# Ekoplazm.net
KiCad netlist of a schematic drawn in EAGLE
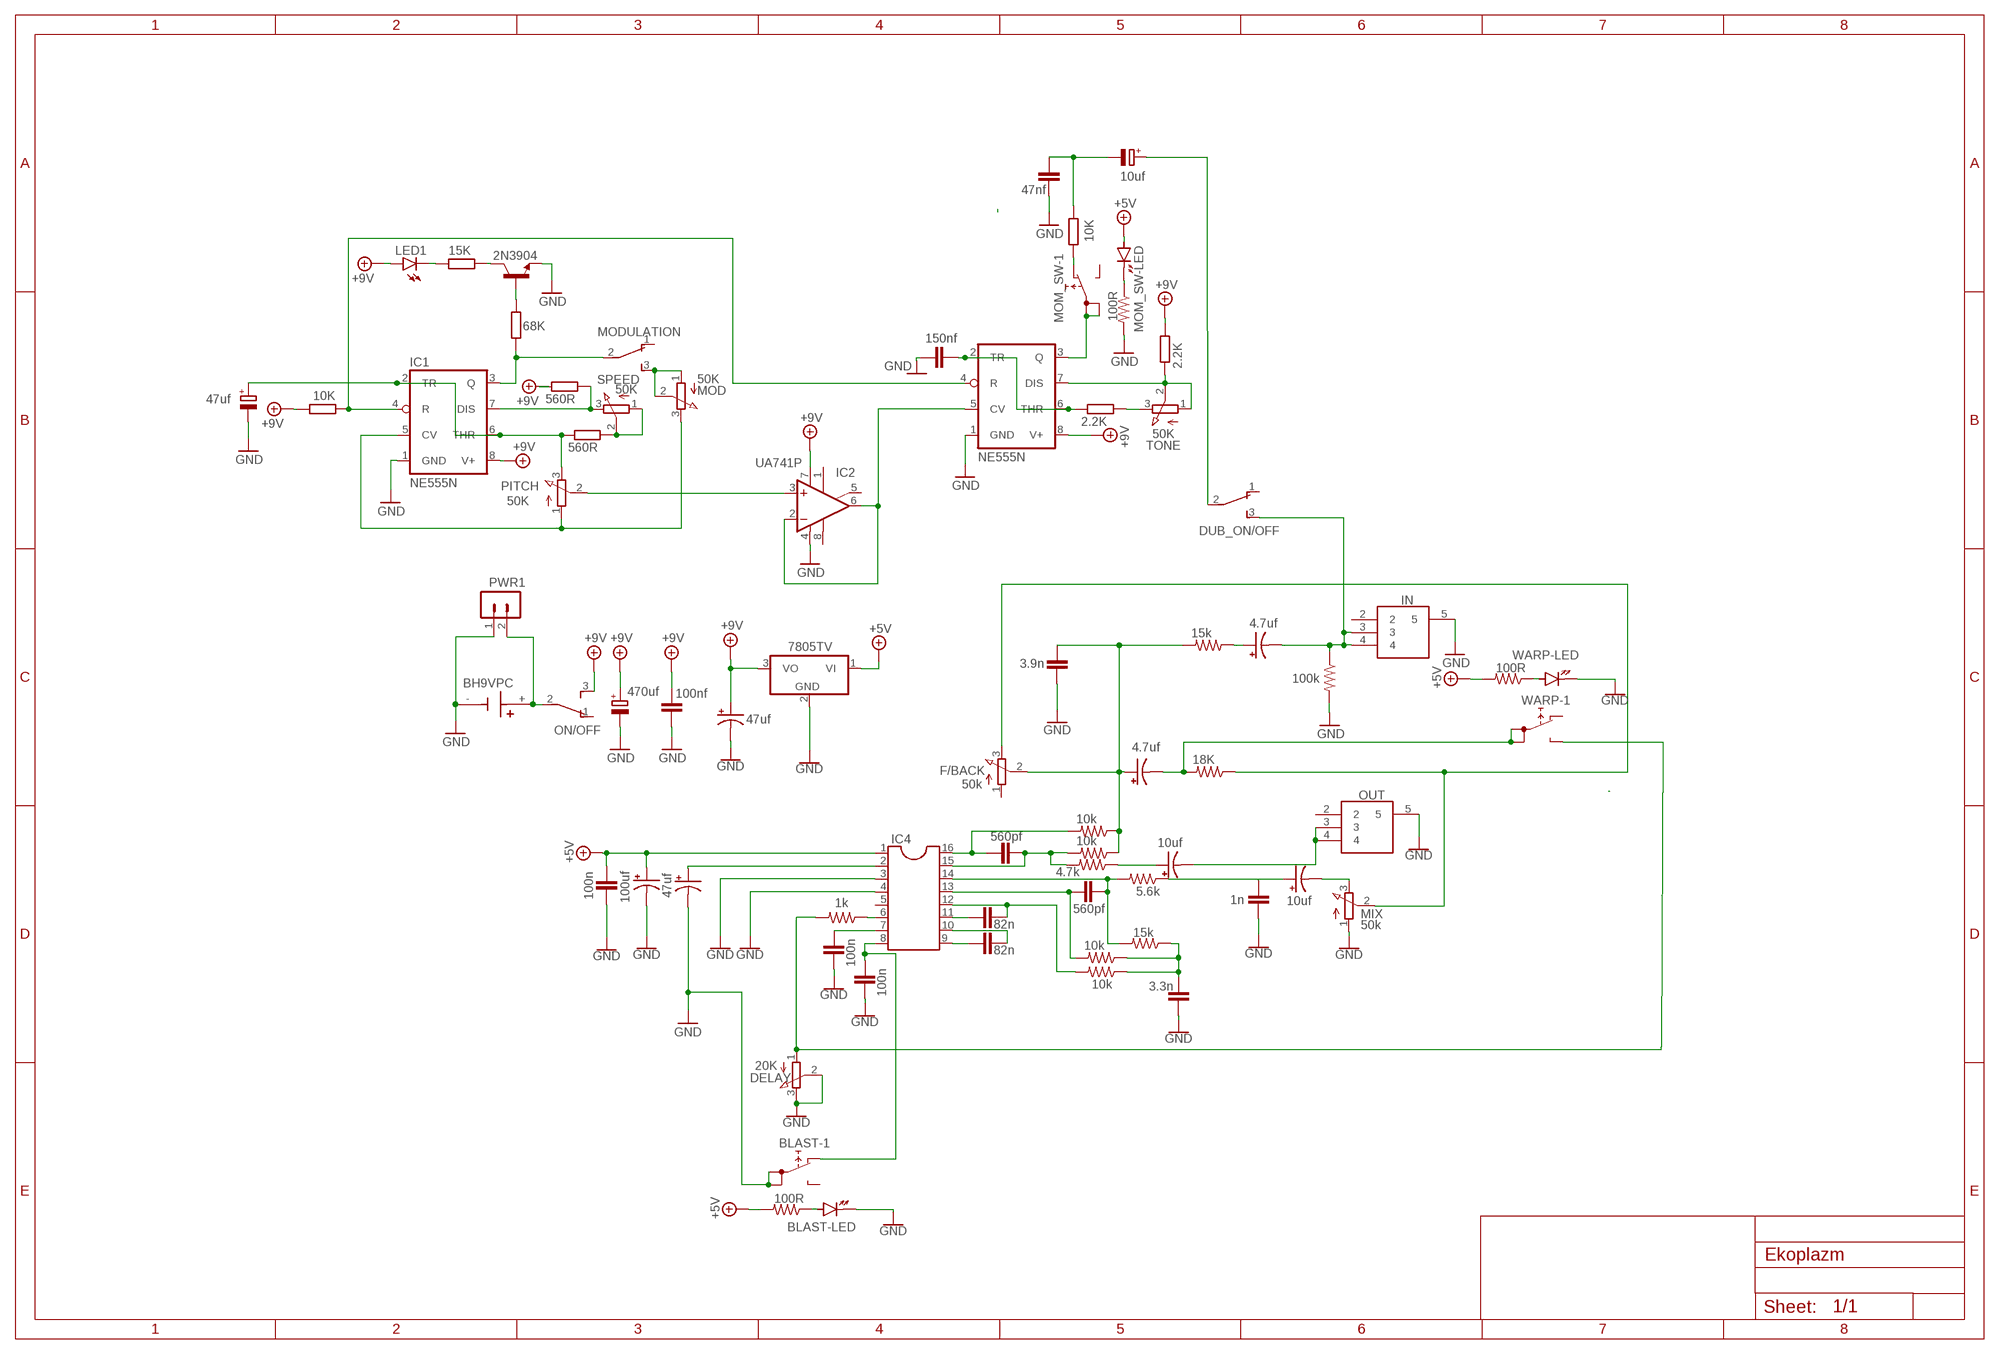
[diagram p0: schematic, sheet 1]

(export (version "E")
  (design (tool "Eeschema 10.0.6"))
  (components
    (comp (ref "10K")
      (value "10K")
      (footprint "eagle-import:0207_10")
      (libsource (lib "eagle-import") (part "R-EU_0207/10"))
    )
    (comp (ref "BLAST")
      (value "5501-1LED")
      (footprint "eagle-import:5501-1LED")
      (libsource (lib "eagle-import") (part "55?-1LED01"))
    )
    (comp (ref "BT1")
      (value "BH9VPC")
      (footprint "eagle-import:BAT_BH9VPC")
      (fields (field (name "MF") "MPD (Memory Protection Devices)"))
      (libsource (lib "eagle-import") (part "BH9VPC"))
    )
    (comp (ref "C1")
      (value "47uf")
      (footprint "eagle-import:E2-5")
      (libsource (lib "eagle-import") (part "CPOL-EUE2-5"))
    )
    (comp (ref "C2")
      (value "470uf")
      (footprint "eagle-import:E3,5-8")
      (libsource (lib "eagle-import") (part "CPOL-EUE3.5-8"))
    )
    (comp (ref "C3")
      (value "100nf")
      (footprint "eagle-import:C050-024X044")
      (libsource (lib "eagle-import") (part "C-EU050-024X044"))
    )
    (comp (ref "C4")
      (value "150nf")
      (footprint "eagle-import:C050-024X044")
      (libsource (lib "eagle-import") (part "C-EU050-024X044"))
    )
    (comp (ref "C5")
      (value "47nf")
      (footprint "eagle-import:C050-024X044")
      (libsource (lib "eagle-import") (part "C-EU050-024X044"))
    )
    (comp (ref "C6")
      (value "10uf")
      (footprint "eagle-import:E2-5")
      (libsource (lib "eagle-import") (part "CPOL-EUE2-5"))
    )
    (comp (ref "C7")
      (value "47uf")
      (footprint "eagle-import:E2-5")
      (libsource (lib "eagle-import") (part "CPOL-USE2-5"))
    )
    (comp (ref "C8")
      (value "1n")
      (footprint "eagle-import:C050-024X044")
      (libsource (lib "eagle-import") (part "C-EU050-024X044"))
    )
    (comp (ref "C9")
      (value "100n")
      (footprint "eagle-import:C050-024X044")
      (libsource (lib "eagle-import") (part "C-EU050-024X044"))
    )
    (comp (ref "C10")
      (value "100n")
      (footprint "eagle-import:C050-024X044")
      (libsource (lib "eagle-import") (part "C-EU050-024X044"))
    )
    (comp (ref "C11")
      (value "100n")
      (footprint "eagle-import:C050-024X044")
      (libsource (lib "eagle-import") (part "C-EU050-024X044"))
    )
    (comp (ref "C12")
      (value "82n")
      (footprint "eagle-import:C050-024X044")
      (libsource (lib "eagle-import") (part "C-EU050-024X044"))
    )
    (comp (ref "C13")
      (value "100uf")
      (footprint "eagle-import:E2-5")
      (libsource (lib "eagle-import") (part "CPOL-USE2-5"))
    )
    (comp (ref "C14")
      (value "47uf")
      (footprint "eagle-import:E2-5")
      (libsource (lib "eagle-import") (part "CPOL-USE2-5"))
    )
    (comp (ref "C15")
      (value "82n")
      (footprint "eagle-import:C050-024X044")
      (libsource (lib "eagle-import") (part "C-EU050-024X044"))
    )
    (comp (ref "C16")
      (value "560pf")
      (footprint "eagle-import:C050-024X044")
      (libsource (lib "eagle-import") (part "C-EU050-024X044"))
    )
    (comp (ref "C17")
      (value "560pf")
      (footprint "eagle-import:C050-024X044")
      (libsource (lib "eagle-import") (part "C-EU050-024X044"))
    )
    (comp (ref "C18")
      (value "10uf")
      (footprint "eagle-import:E2-5")
      (libsource (lib "eagle-import") (part "CPOL-USE2-5"))
    )
    (comp (ref "C19")
      (value "3.3n")
      (footprint "eagle-import:C050-024X044")
      (libsource (lib "eagle-import") (part "C-EU050-024X044"))
    )
    (comp (ref "C20")
      (value "10uf")
      (footprint "eagle-import:E2-5")
      (libsource (lib "eagle-import") (part "CPOL-USE2-5"))
    )
    (comp (ref "C21")
      (value "4.7uf")
      (footprint "eagle-import:E2-5")
      (libsource (lib "eagle-import") (part "CPOL-USE2-5"))
    )
    (comp (ref "C22")
      (value "3.9n")
      (footprint "eagle-import:C050-024X044")
      (libsource (lib "eagle-import") (part "C-EU050-024X044"))
    )
    (comp (ref "C23")
      (value "4.7uf")
      (footprint "eagle-import:E2-5")
      (libsource (lib "eagle-import") (part "CPOL-USE2-5"))
    )
    (comp (ref "DELAY")
      (value "20K")
      (footprint "eagle-import:EVUFXL")
      (libsource (lib "eagle-import") (part "EVULF2"))
    )
    (comp (ref "DUB_ON/OFF")
      (value "TL36PO")
      (footprint "eagle-import:TL3XPO")
      (libsource (lib "eagle-import") (part "TL36PO"))
    )
    (comp (ref "F/BACK")
      (value "50k")
      (footprint "eagle-import:EVUFXL")
      (libsource (lib "eagle-import") (part "EVULF2"))
    )
    (comp (ref "IC1")
      (value "NE555N")
      (footprint "eagle-import:DIL08")
      (libsource (lib "eagle-import") (part "555NNE"))
    )
    (comp (ref "IC2")
      (value "UA741P")
      (footprint "eagle-import:DIL08")
      (libsource (lib "eagle-import") (part "741PUA"))
    )
    (comp (ref "IC3")
      (value "NE555N")
      (footprint "eagle-import:DIL08")
      (libsource (lib "eagle-import") (part "555NNE"))
    )
    (comp (ref "IC4")
      (value "DIL16")
      (footprint "eagle-import:DIL16")
      (libsource (lib "eagle-import") (part "DIL16"))
    )
    (comp (ref "IC5")
      (value "7805TV")
      (footprint "eagle-import:TO220V")
      (libsource (lib "eagle-import") (part "78TV05"))
    )
    (comp (ref "IN")
      (value "PJ-320A")
      (footprint "eagle-import:PJ320A")
      (libsource (lib "eagle-import") (part "PJ-320A"))
    )
    (comp (ref "LED1")
      (value "LED3MM")
      (footprint "eagle-import:LED3MM")
      (libsource (lib "eagle-import") (part "LED3MM"))
    )
    (comp (ref "MIX")
      (value "50k")
      (footprint "eagle-import:EVUFXL")
      (libsource (lib "eagle-import") (part "EVULF2"))
    )
    (comp (ref "MOD")
      (value "50K")
      (footprint "eagle-import:EVUF")
      (libsource (lib "eagle-import") (part "EVUAF2"))
    )
    (comp (ref "MODULATION")
      (value "TL36PO")
      (footprint "eagle-import:TL3XPO")
      (libsource (lib "eagle-import") (part "TL36PO"))
    )
    (comp (ref "MOM_SW")
      (value "5501-1LED")
      (footprint "eagle-import:5501-1LED")
      (libsource (lib "eagle-import") (part "55?-1LED01"))
    )
    (comp (ref "ON/OFF")
      (value "TL36PO")
      (footprint "eagle-import:TL3XPO")
      (libsource (lib "eagle-import") (part "TL36PO"))
    )
    (comp (ref "OUT")
      (value "PJ-320A")
      (footprint "eagle-import:PJ320A")
      (libsource (lib "eagle-import") (part "PJ-320A"))
    )
    (comp (ref "PITCH")
      (value "50K")
      (footprint "eagle-import:EVUF")
      (libsource (lib "eagle-import") (part "EVUAF2"))
    )
    (comp (ref "PWR1")
      (value "B2B-PH-K-S")
      (footprint "eagle-import:B2B-PH-K-S")
      (libsource (lib "eagle-import") (part "B2B-PH-K-S"))
    )
    (comp (ref "R1")
      (value "10K")
      (footprint "eagle-import:0207_10")
      (libsource (lib "eagle-import") (part "R-EU_0207/10"))
    )
    (comp (ref "R2")
      (value "560R")
      (footprint "eagle-import:0207_10")
      (libsource (lib "eagle-import") (part "R-EU_0207/10"))
    )
    (comp (ref "R3")
      (value "68K")
      (footprint "eagle-import:0207_10")
      (libsource (lib "eagle-import") (part "R-EU_0207/10"))
    )
    (comp (ref "R4")
      (value "15K")
      (footprint "eagle-import:0207_10")
      (libsource (lib "eagle-import") (part "R-EU_0207/10"))
    )
    (comp (ref "R5")
      (value "2.2K")
      (footprint "eagle-import:0207_10")
      (libsource (lib "eagle-import") (part "R-EU_0207/10"))
    )
    (comp (ref "R6")
      (value "2.2K")
      (footprint "eagle-import:0207_10")
      (libsource (lib "eagle-import") (part "R-EU_0207/10"))
    )
    (comp (ref "R7")
      (value "560R")
      (footprint "eagle-import:0207_10")
      (libsource (lib "eagle-import") (part "R-EU_0207/10"))
    )
    (comp (ref "R8")
      (value "10k")
      (footprint "eagle-import:0207_10")
      (libsource (lib "eagle-import") (part "R-US_0207/10"))
    )
    (comp (ref "R10")
      (value "5.6k")
      (footprint "eagle-import:0207_10")
      (libsource (lib "eagle-import") (part "R-US_0207/10"))
    )
    (comp (ref "R11")
      (value "1k")
      (footprint "eagle-import:0207_10")
      (libsource (lib "eagle-import") (part "R-US_0207/10"))
    )
    (comp (ref "R12")
      (value "10k")
      (footprint "eagle-import:0207_10")
      (libsource (lib "eagle-import") (part "R-US_0207/10"))
    )
    (comp (ref "R13")
      (value "15k")
      (footprint "eagle-import:0207_10")
      (libsource (lib "eagle-import") (part "R-US_0207/10"))
    )
    (comp (ref "R14")
      (value "100R")
      (footprint "eagle-import:0207_10")
      (libsource (lib "eagle-import") (part "R-US_0207/10"))
    )
    (comp (ref "R15")
      (value "10k")
      (footprint "eagle-import:0207_10")
      (libsource (lib "eagle-import") (part "R-US_0207/10"))
    )
    (comp (ref "R16")
      (value "4.7k")
      (footprint "eagle-import:0207_10")
      (libsource (lib "eagle-import") (part "R-US_0207/10"))
    )
    (comp (ref "R17")
      (value "10k")
      (footprint "eagle-import:0207_10")
      (libsource (lib "eagle-import") (part "R-US_0207/10"))
    )
    (comp (ref "R18")
      (value "18K")
      (footprint "eagle-import:0207_10")
      (libsource (lib "eagle-import") (part "R-US_0207/10"))
    )
    (comp (ref "R19")
      (value "15k")
      (footprint "eagle-import:0207_10")
      (libsource (lib "eagle-import") (part "R-US_0207/10"))
    )
    (comp (ref "R20")
      (value "100k")
      (footprint "eagle-import:0207_10")
      (libsource (lib "eagle-import") (part "R-US_0207/10"))
    )
    (comp (ref "R21")
      (value "100R")
      (footprint "eagle-import:0207_10")
      (libsource (lib "eagle-import") (part "R-US_0207/10"))
    )
    (comp (ref "R22")
      (value "100R")
      (footprint "eagle-import:0207_10")
      (libsource (lib "eagle-import") (part "R-US_0207/10"))
    )
    (comp (ref "SPEED")
      (value "50K")
      (footprint "eagle-import:EVUF")
      (libsource (lib "eagle-import") (part "EVUAF2"))
    )
    (comp (ref "T1")
      (value "2N3904")
      (footprint "eagle-import:TO92")
      (libsource (lib "eagle-import") (part "2N3904"))
    )
    (comp (ref "TONE")
      (value "50K")
      (footprint "eagle-import:EVUF")
      (libsource (lib "eagle-import") (part "EVUAF2"))
    )
    (comp (ref "WARP")
      (value "5501-1LED")
      (footprint "eagle-import:5501-1LED")
      (libsource (lib "eagle-import") (part "55?-1LED01"))
    )
  )
  (nets
    (net (code "1") (name "+5V") (class "Default")
      (node (ref "C13") (pin "+") (pinfunction "+_+") (pintype "passive"))
      (node (ref "C9") (pin "1") (pinfunction "1_1") (pintype "passive"))
      (node (ref "IC4") (pin "1") (pinfunction "1_1") (pintype "passive"))
      (node (ref "IC5") (pin "1") (pinfunction "VI_1") (pintype "input"))
      (node (ref "MOM_SW") (pin "+") (pinfunction "A_+") (pintype "passive"))
      (node (ref "R14") (pin "2") (pinfunction "2_2") (pintype "passive"))
      (node (ref "R22") (pin "2") (pinfunction "2_2") (pintype "passive"))
    )
    (net (code "2") (name "+9V") (class "Default")
      (node (ref "C14") (pin "+") (pinfunction "+_+") (pintype "passive"))
      (node (ref "C2") (pin "+") (pinfunction "+_+") (pintype "passive"))
      (node (ref "C3") (pin "1") (pinfunction "1_1") (pintype "passive"))
      (node (ref "IC1") (pin "8") (pinfunction "V+_8") (pintype "power_in"))
      (node (ref "IC2") (pin "7") (pinfunction "V+_7") (pintype "power_in"))
      (node (ref "IC3") (pin "8") (pinfunction "V+_8") (pintype "power_in"))
      (node (ref "IC5") (pin "3") (pinfunction "VO_3") (pintype "passive"))
      (node (ref "LED1") (pin "A") (pinfunction "A_A") (pintype "passive"))
      (node (ref "ON/OFF") (pin "3") (pinfunction "S_3") (pintype "passive"))
      (node (ref "R1") (pin "1") (pinfunction "1_1") (pintype "passive"))
      (node (ref "R6") (pin "2") (pinfunction "2_2") (pintype "passive"))
      (node (ref "R7") (pin "1") (pinfunction "1_1") (pintype "passive"))
    )
    (net (code "3") (name "GND") (class "Default")
      (node (ref "BLAST") (pin "-") (pinfunction "K_-") (pintype "passive"))
      (node (ref "BLAST") (pin "1A") (pinfunction "1A_1A") (pintype "passive"))
      (node (ref "BLAST") (pin "1B") (pinfunction "1B_1B") (pintype "passive"))
      (node (ref "BT1") (pin "-") (pinfunction "-_-") (pintype "passive"))
      (node (ref "C1") (pin "-") (pinfunction "-_-") (pintype "passive"))
      (node (ref "C10") (pin "2") (pinfunction "2_2") (pintype "passive"))
      (node (ref "C11") (pin "2") (pinfunction "2_2") (pintype "passive"))
      (node (ref "C13") (pin "-") (pinfunction "-_-") (pintype "passive"))
      (node (ref "C14") (pin "-") (pinfunction "-_-") (pintype "passive"))
      (node (ref "C19") (pin "1") (pinfunction "1_1") (pintype "passive"))
      (node (ref "C2") (pin "-") (pinfunction "-_-") (pintype "passive"))
      (node (ref "C22") (pin "2") (pinfunction "2_2") (pintype "passive"))
      (node (ref "C3") (pin "2") (pinfunction "2_2") (pintype "passive"))
      (node (ref "C4") (pin "1") (pinfunction "1_1") (pintype "passive"))
      (node (ref "C5") (pin "1") (pinfunction "1_1") (pintype "passive"))
      (node (ref "C7") (pin "-") (pinfunction "-_-") (pintype "passive"))
      (node (ref "C8") (pin "2") (pinfunction "2_2") (pintype "passive"))
      (node (ref "C9") (pin "2") (pinfunction "2_2") (pintype "passive"))
      (node (ref "DELAY") (pin "2") (pinfunction "S_2") (pintype "passive"))
      (node (ref "DELAY") (pin "3") (pinfunction "E_3") (pintype "passive"))
      (node (ref "IC1") (pin "1") (pinfunction "GND_1") (pintype "power_in"))
      (node (ref "IC2") (pin "4") (pinfunction "V-_4") (pintype "power_in"))
      (node (ref "IC3") (pin "1") (pinfunction "GND_1") (pintype "power_in"))
      (node (ref "IC4") (pin "3") (pinfunction "3_3") (pintype "passive"))
      (node (ref "IC4") (pin "4") (pinfunction "4_4") (pintype "passive"))
      (node (ref "IC5") (pin "2") (pinfunction "GND_2") (pintype "passive"))
      (node (ref "IN") (pin "5") (pinfunction "5_5") (pintype "bidirectional"))
      (node (ref "MIX") (pin "1") (pinfunction "A_1") (pintype "passive"))
      (node (ref "OUT") (pin "5") (pinfunction "5_5") (pintype "bidirectional"))
      (node (ref "PWR1") (pin "1") (pinfunction "1_1") (pintype "passive"))
      (node (ref "R20") (pin "2") (pinfunction "2_2") (pintype "passive"))
      (node (ref "R21") (pin "2") (pinfunction "2_2") (pintype "passive"))
      (node (ref "T1") (pin "3") (pinfunction "E_3") (pintype "passive"))
      (node (ref "WARP") (pin "-") (pinfunction "K_-") (pintype "passive"))
    )
    (net (code "4") (name "Net-(10K-Pad1)") (class "Default")
      (node (ref "10K") (pin "1") (pinfunction "1_1") (pintype "passive"))
      (node (ref "MOM_SW") (pin "NC") (pinfunction "NC_NC") (pintype "passive"))
    )
    (net (code "5") (name "Net-(10K-Pad2)") (class "Default")
      (node (ref "10K") (pin "2") (pinfunction "2_2") (pintype "passive"))
      (node (ref "C5") (pin "2") (pinfunction "2_2") (pintype "passive"))
      (node (ref "C6") (pin "-") (pinfunction "-_-") (pintype "passive"))
    )
    (net (code "6") (name "Net-(BLAST-PadNC)") (class "Default")
      (node (ref "BLAST") (pin "NC") (pinfunction "NC_NC") (pintype "passive"))
      (node (ref "C11") (pin "1") (pinfunction "1_1") (pintype "passive"))
      (node (ref "IC4") (pin "8") (pinfunction "8_8") (pintype "passive"))
    )
    (net (code "7") (name "Net-(BLASTB-A)") (class "Default")
      (node (ref "BLAST") (pin "+") (pinfunction "A_+") (pintype "passive"))
      (node (ref "R14") (pin "1") (pinfunction "1_1") (pintype "passive"))
    )
    (net (code "8") (name "Net-(C7-Pad+)") (class "Default")
      (node (ref "C7") (pin "+") (pinfunction "+_+") (pintype "passive"))
      (node (ref "IC4") (pin "2") (pinfunction "2_2") (pintype "passive"))
    )
    (net (code "9") (name "Net-(C10-Pad1)") (class "Default")
      (node (ref "C10") (pin "1") (pinfunction "1_1") (pintype "passive"))
      (node (ref "IC4") (pin "7") (pinfunction "7_7") (pintype "passive"))
    )
    (net (code "10") (name "Net-(C12-Pad1)") (class "Default")
      (node (ref "C12") (pin "1") (pinfunction "1_1") (pintype "passive"))
      (node (ref "IC4") (pin "9") (pinfunction "9_9") (pintype "passive"))
    )
    (net (code "11") (name "Net-(C12-Pad2)") (class "Default")
      (node (ref "C12") (pin "2") (pinfunction "2_2") (pintype "passive"))
      (node (ref "IC4") (pin "10") (pinfunction "10_10") (pintype "passive"))
    )
    (net (code "12") (name "Net-(C15-Pad1)") (class "Default")
      (node (ref "C15") (pin "1") (pinfunction "1_1") (pintype "passive"))
      (node (ref "IC4") (pin "11") (pinfunction "11_11") (pintype "passive"))
    )
    (net (code "13") (name "Net-(C15-Pad2)") (class "Default")
      (node (ref "C15") (pin "2") (pinfunction "2_2") (pintype "passive"))
      (node (ref "IC4") (pin "12") (pinfunction "12_12") (pintype "passive"))
      (node (ref "R8") (pin "2") (pinfunction "2_2") (pintype "passive"))
    )
    (net (code "14") (name "Net-(C16-Pad1)") (class "Default")
      (node (ref "C16") (pin "1") (pinfunction "1_1") (pintype "passive"))
      (node (ref "IC4") (pin "13") (pinfunction "13_13") (pintype "passive"))
      (node (ref "R12") (pin "2") (pinfunction "2_2") (pintype "passive"))
    )
    (net (code "15") (name "Net-(C16-Pad2)") (class "Default")
      (node (ref "C16") (pin "2") (pinfunction "2_2") (pintype "passive"))
      (node (ref "IC4") (pin "14") (pinfunction "14_14") (pintype "passive"))
      (node (ref "R10") (pin "2") (pinfunction "2_2") (pintype "passive"))
      (node (ref "R13") (pin "2") (pinfunction "2_2") (pintype "passive"))
    )
    (net (code "16") (name "Net-(C17-Pad1)") (class "Default")
      (node (ref "C17") (pin "1") (pinfunction "1_1") (pintype "passive"))
      (node (ref "IC4") (pin "16") (pinfunction "16_16") (pintype "passive"))
      (node (ref "R17") (pin "2") (pinfunction "2_2") (pintype "passive"))
    )
    (net (code "17") (name "Net-(C17-Pad2)") (class "Default")
      (node (ref "C17") (pin "2") (pinfunction "2_2") (pintype "passive"))
      (node (ref "IC4") (pin "15") (pinfunction "15_15") (pintype "passive"))
      (node (ref "R15") (pin "2") (pinfunction "2_2") (pintype "passive"))
      (node (ref "R16") (pin "2") (pinfunction "2_2") (pintype "passive"))
    )
    (net (code "18") (name "Net-(C18-Pad+)") (class "Default")
      (node (ref "C18") (pin "+") (pinfunction "+_+") (pintype "passive"))
      (node (ref "C8") (pin "1") (pinfunction "1_1") (pintype "passive"))
      (node (ref "R10") (pin "1") (pinfunction "1_1") (pintype "passive"))
    )
    (net (code "19") (name "Net-(C19-Pad2)") (class "Default")
      (node (ref "C19") (pin "2") (pinfunction "2_2") (pintype "passive"))
      (node (ref "R12") (pin "1") (pinfunction "1_1") (pintype "passive"))
      (node (ref "R13") (pin "1") (pinfunction "1_1") (pintype "passive"))
      (node (ref "R8") (pin "1") (pinfunction "1_1") (pintype "passive"))
    )
    (net (code "20") (name "Net-(C20-Pad+)") (class "Default")
      (node (ref "C20") (pin "+") (pinfunction "+_+") (pintype "passive"))
      (node (ref "R16") (pin "1") (pinfunction "1_1") (pintype "passive"))
    )
    (net (code "21") (name "Net-(C20-Pad-)") (class "Default")
      (node (ref "C20") (pin "-") (pinfunction "-_-") (pintype "passive"))
      (node (ref "OUT") (pin "3") (pinfunction "3_3") (pintype "bidirectional"))
      (node (ref "OUT") (pin "4") (pinfunction "4_4") (pintype "bidirectional"))
    )
    (net (code "22") (name "Net-(C21-Pad-)") (class "Default")
      (node (ref "C21") (pin "-") (pinfunction "-_-") (pintype "passive"))
      (node (ref "R18") (pin "2") (pinfunction "2_2") (pintype "passive"))
      (node (ref "WARP") (pin "1A") (pinfunction "1A_1A") (pintype "passive"))
      (node (ref "WARP") (pin "1B") (pinfunction "1B_1B") (pintype "passive"))
    )
    (net (code "23") (name "Net-(C23-Pad+)") (class "Default")
      (node (ref "C23") (pin "+") (pinfunction "+_+") (pintype "passive"))
      (node (ref "R19") (pin "1") (pinfunction "1_1") (pintype "passive"))
    )
    (net (code "24") (name "Net-(DELAY-A)") (class "Default")
      (node (ref "DELAY") (pin "1") (pinfunction "A_1") (pintype "passive"))
      (node (ref "R11") (pin "2") (pinfunction "2_2") (pintype "passive"))
      (node (ref "WARP") (pin "NO") (pinfunction "NO_NO") (pintype "passive"))
    )
    (net (code "25") (name "Net-(DUB_ON/OFF-P)") (class "Default")
      (node (ref "C6") (pin "+") (pinfunction "+_+") (pintype "passive"))
      (node (ref "DUB_ON/OFF") (pin "2") (pinfunction "P_2") (pintype "passive"))
    )
    (net (code "26") (name "Net-(DUB_ON/OFF-S)") (class "Default")
      (node (ref "C23") (pin "-") (pinfunction "-_-") (pintype "passive"))
      (node (ref "DUB_ON/OFF") (pin "3") (pinfunction "S_3") (pintype "passive"))
      (node (ref "IN") (pin "3") (pinfunction "3_3") (pintype "bidirectional"))
      (node (ref "IN") (pin "4") (pinfunction "4_4") (pintype "bidirectional"))
      (node (ref "R20") (pin "1") (pinfunction "1_1") (pintype "passive"))
    )
    (net (code "27") (name "Net-(F/BACK-E)") (class "Default")
      (node (ref "F/BACK") (pin "3") (pinfunction "E_3") (pintype "passive"))
      (node (ref "MIX") (pin "2") (pinfunction "S_2") (pintype "passive"))
      (node (ref "R18") (pin "1") (pinfunction "1_1") (pintype "passive"))
    )
    (net (code "28") (name "Net-(F/BACK-S)") (class "Default")
      (node (ref "C21") (pin "+") (pinfunction "+_+") (pintype "passive"))
      (node (ref "C22") (pin "1") (pinfunction "1_1") (pintype "passive"))
      (node (ref "F/BACK") (pin "2") (pinfunction "S_2") (pintype "passive"))
      (node (ref "R15") (pin "1") (pinfunction "1_1") (pintype "passive"))
      (node (ref "R17") (pin "1") (pinfunction "1_1") (pintype "passive"))
      (node (ref "R19") (pin "2") (pinfunction "2_2") (pintype "passive"))
    )
    (net (code "29") (name "Net-(IC1-CV)") (class "Default")
      (node (ref "IC1") (pin "5") (pinfunction "CV_5") (pintype "input"))
      (node (ref "MOD") (pin "3") (pinfunction "E_3") (pintype "passive"))
      (node (ref "PITCH") (pin "1") (pinfunction "A_1") (pintype "passive"))
    )
    (net (code "30") (name "Net-(IC1-DIS)") (class "Default")
      (node (ref "IC1") (pin "7") (pinfunction "DIS_7") (pintype "input"))
      (node (ref "R7") (pin "2") (pinfunction "2_2") (pintype "passive"))
      (node (ref "SPEED") (pin "3") (pinfunction "E_3") (pintype "passive"))
    )
    (net (code "31") (name "Net-(IC1-Q)") (class "Default")
      (node (ref "IC1") (pin "3") (pinfunction "Q_3") (pintype "output"))
      (node (ref "MODULATION") (pin "2") (pinfunction "P_2") (pintype "passive"))
      (node (ref "R3") (pin "1") (pinfunction "1_1") (pintype "passive"))
    )
    (net (code "32") (name "Net-(IC1-R)") (class "Default")
      (node (ref "IC1") (pin "4") (pinfunction "R_4") (pintype "input"))
      (node (ref "IC3") (pin "4") (pinfunction "R_4") (pintype "input"))
      (node (ref "R1") (pin "2") (pinfunction "2_2") (pintype "passive"))
    )
    (net (code "33") (name "Net-(IC1-THR)") (class "Default")
      (node (ref "C1") (pin "+") (pinfunction "+_+") (pintype "passive"))
      (node (ref "IC1") (pin "2") (pinfunction "TR_2") (pintype "input"))
      (node (ref "IC1") (pin "6") (pinfunction "THR_6") (pintype "input"))
      (node (ref "PITCH") (pin "3") (pinfunction "E_3") (pintype "passive"))
      (node (ref "R2") (pin "1") (pinfunction "1_1") (pintype "passive"))
    )
    (net (code "34") (name "Net-(IC2-+IN)") (class "Default")
      (node (ref "IC2") (pin "3") (pinfunction "+IN_3") (pintype "input"))
      (node (ref "PITCH") (pin "2") (pinfunction "S_2") (pintype "passive"))
    )
    (net (code "35") (name "Net-(IC2--IN)") (class "Default")
      (node (ref "IC2") (pin "2") (pinfunction "-IN_2") (pintype "input"))
      (node (ref "IC2") (pin "6") (pinfunction "OUT_6") (pintype "output"))
      (node (ref "IC3") (pin "5") (pinfunction "CV_5") (pintype "input"))
    )
    (net (code "36") (name "Net-(IC3-DIS)") (class "Default")
      (node (ref "IC3") (pin "7") (pinfunction "DIS_7") (pintype "input"))
      (node (ref "R6") (pin "1") (pinfunction "1_1") (pintype "passive"))
      (node (ref "TONE") (pin "1") (pinfunction "A_1") (pintype "passive"))
      (node (ref "TONE") (pin "2") (pinfunction "S_2") (pintype "passive"))
    )
    (net (code "37") (name "Net-(IC3-Q)") (class "Default")
      (node (ref "IC3") (pin "3") (pinfunction "Q_3") (pintype "output"))
      (node (ref "MOM_SW") (pin "1A") (pinfunction "1A_1A") (pintype "passive"))
      (node (ref "MOM_SW") (pin "1B") (pinfunction "1B_1B") (pintype "passive"))
    )
    (net (code "38") (name "Net-(IC3-THR)") (class "Default")
      (node (ref "C4") (pin "2") (pinfunction "2_2") (pintype "passive"))
      (node (ref "IC3") (pin "2") (pinfunction "TR_2") (pintype "input"))
      (node (ref "IC3") (pin "6") (pinfunction "THR_6") (pintype "input"))
      (node (ref "R5") (pin "1") (pinfunction "1_1") (pintype "passive"))
    )
    (net (code "39") (name "Net-(IC4-Pad6)") (class "Default")
      (node (ref "IC4") (pin "6") (pinfunction "6_6") (pintype "passive"))
      (node (ref "R11") (pin "1") (pinfunction "1_1") (pintype "passive"))
    )
    (net (code "40") (name "Net-(LED1-C)") (class "Default")
      (node (ref "LED1") (pin "K") (pinfunction "C_K") (pintype "passive"))
      (node (ref "R4") (pin "2") (pinfunction "2_2") (pintype "passive"))
    )
    (net (code "41") (name "Net-(MIX-E)") (class "Default")
      (node (ref "C18") (pin "-") (pinfunction "-_-") (pintype "passive"))
      (node (ref "MIX") (pin "3") (pinfunction "E_3") (pintype "passive"))
    )
    (net (code "42") (name "Net-(MOD-A)") (class "Default")
      (node (ref "MOD") (pin "1") (pinfunction "A_1") (pintype "passive"))
      (node (ref "MOD") (pin "2") (pinfunction "S_2") (pintype "passive"))
      (node (ref "MODULATION") (pin "3") (pinfunction "S_3") (pintype "passive"))
    )
    (net (code "43") (name "Net-(MOM_SWB-K)") (class "Default")
      (node (ref "MOM_SW") (pin "-") (pinfunction "K_-") (pintype "passive"))
      (node (ref "R21") (pin "1") (pinfunction "1_1") (pintype "passive"))
    )
    (net (code "44") (name "Net-(ON/OFF-P)") (class "Default")
      (node (ref "BT1") (pin "+") (pinfunction "+_+") (pintype "passive"))
      (node (ref "ON/OFF") (pin "2") (pinfunction "P_2") (pintype "passive"))
      (node (ref "PWR1") (pin "2") (pinfunction "2_2") (pintype "passive"))
    )
    (net (code "45") (name "Net-(SPEED-A)") (class "Default")
      (node (ref "R2") (pin "2") (pinfunction "2_2") (pintype "passive"))
      (node (ref "SPEED") (pin "1") (pinfunction "A_1") (pintype "passive"))
      (node (ref "SPEED") (pin "2") (pinfunction "S_2") (pintype "passive"))
    )
    (net (code "46") (name "Net-(T1-B)") (class "Default")
      (node (ref "R3") (pin "2") (pinfunction "2_2") (pintype "passive"))
      (node (ref "T1") (pin "2") (pinfunction "B_2") (pintype "passive"))
    )
    (net (code "47") (name "Net-(T1-C)") (class "Default")
      (node (ref "R4") (pin "1") (pinfunction "1_1") (pintype "passive"))
      (node (ref "T1") (pin "1") (pinfunction "C_1") (pintype "passive"))
    )
    (net (code "48") (name "Net-(TONE-E)") (class "Default")
      (node (ref "R5") (pin "2") (pinfunction "2_2") (pintype "passive"))
      (node (ref "TONE") (pin "3") (pinfunction "E_3") (pintype "passive"))
    )
    (net (code "49") (name "Net-(WARPB-A)") (class "Default")
      (node (ref "R22") (pin "1") (pinfunction "1_1") (pintype "passive"))
      (node (ref "WARP") (pin "+") (pinfunction "A_+") (pintype "passive"))
    )
    (net (code "50") (name "unconnected-(BLAST-PadNO)") (class "Default")
      (node (ref "BLAST") (pin "NO") (pinfunction "NO_NO") (pintype "passive"))
    )
    (net (code "51") (name "unconnected-(DUB_ON/OFF-O-Pad1)") (class "Default")
      (node (ref "DUB_ON/OFF") (pin "1") (pinfunction "O_1") (pintype "passive"))
    )
    (net (code "52") (name "unconnected-(F/BACK-A-Pad1)") (class "Default")
      (node (ref "F/BACK") (pin "1") (pinfunction "A_1") (pintype "passive"))
    )
    (net (code "53") (name "unconnected-(IC2-ON1-Pad1)") (class "Default")
      (node (ref "IC2") (pin "1") (pinfunction "ON1_1") (pintype "passive"))
    )
    (net (code "54") (name "unconnected-(IC2-ON2-Pad5)") (class "Default")
      (node (ref "IC2") (pin "5") (pinfunction "ON2_5") (pintype "passive"))
    )
    (net (code "55") (name "unconnected-(IC2-OPT-Pad8)") (class "Default")
      (node (ref "IC2") (pin "8") (pinfunction "OPT_8") (pintype "passive"))
    )
    (net (code "56") (name "unconnected-(IC4-Pad5)") (class "Default")
      (node (ref "IC4") (pin "5") (pinfunction "5_5") (pintype "passive"))
    )
    (net (code "57") (name "unconnected-(IN-Pad2)") (class "Default")
      (node (ref "IN") (pin "2") (pinfunction "2_2") (pintype "bidirectional"))
    )
    (net (code "58") (name "unconnected-(MODULATION-O-Pad1)") (class "Default")
      (node (ref "MODULATION") (pin "1") (pinfunction "O_1") (pintype "passive"))
    )
    (net (code "59") (name "unconnected-(MOM_SW-PadNO)") (class "Default")
      (node (ref "MOM_SW") (pin "NO") (pinfunction "NO_NO") (pintype "passive"))
    )
    (net (code "60") (name "unconnected-(ON/OFF-O-Pad1)") (class "Default")
      (node (ref "ON/OFF") (pin "1") (pinfunction "O_1") (pintype "passive"))
    )
    (net (code "61") (name "unconnected-(OUT-Pad2)") (class "Default")
      (node (ref "OUT") (pin "2") (pinfunction "2_2") (pintype "bidirectional"))
    )
    (net (code "62") (name "unconnected-(WARP-PadNC)") (class "Default")
      (node (ref "WARP") (pin "NC") (pinfunction "NC_NC") (pintype "passive"))
    )
  )
)
